# 2014_FDP_SCHEMA.net
KiCad netlist of a schematic drawn in Altium Designer
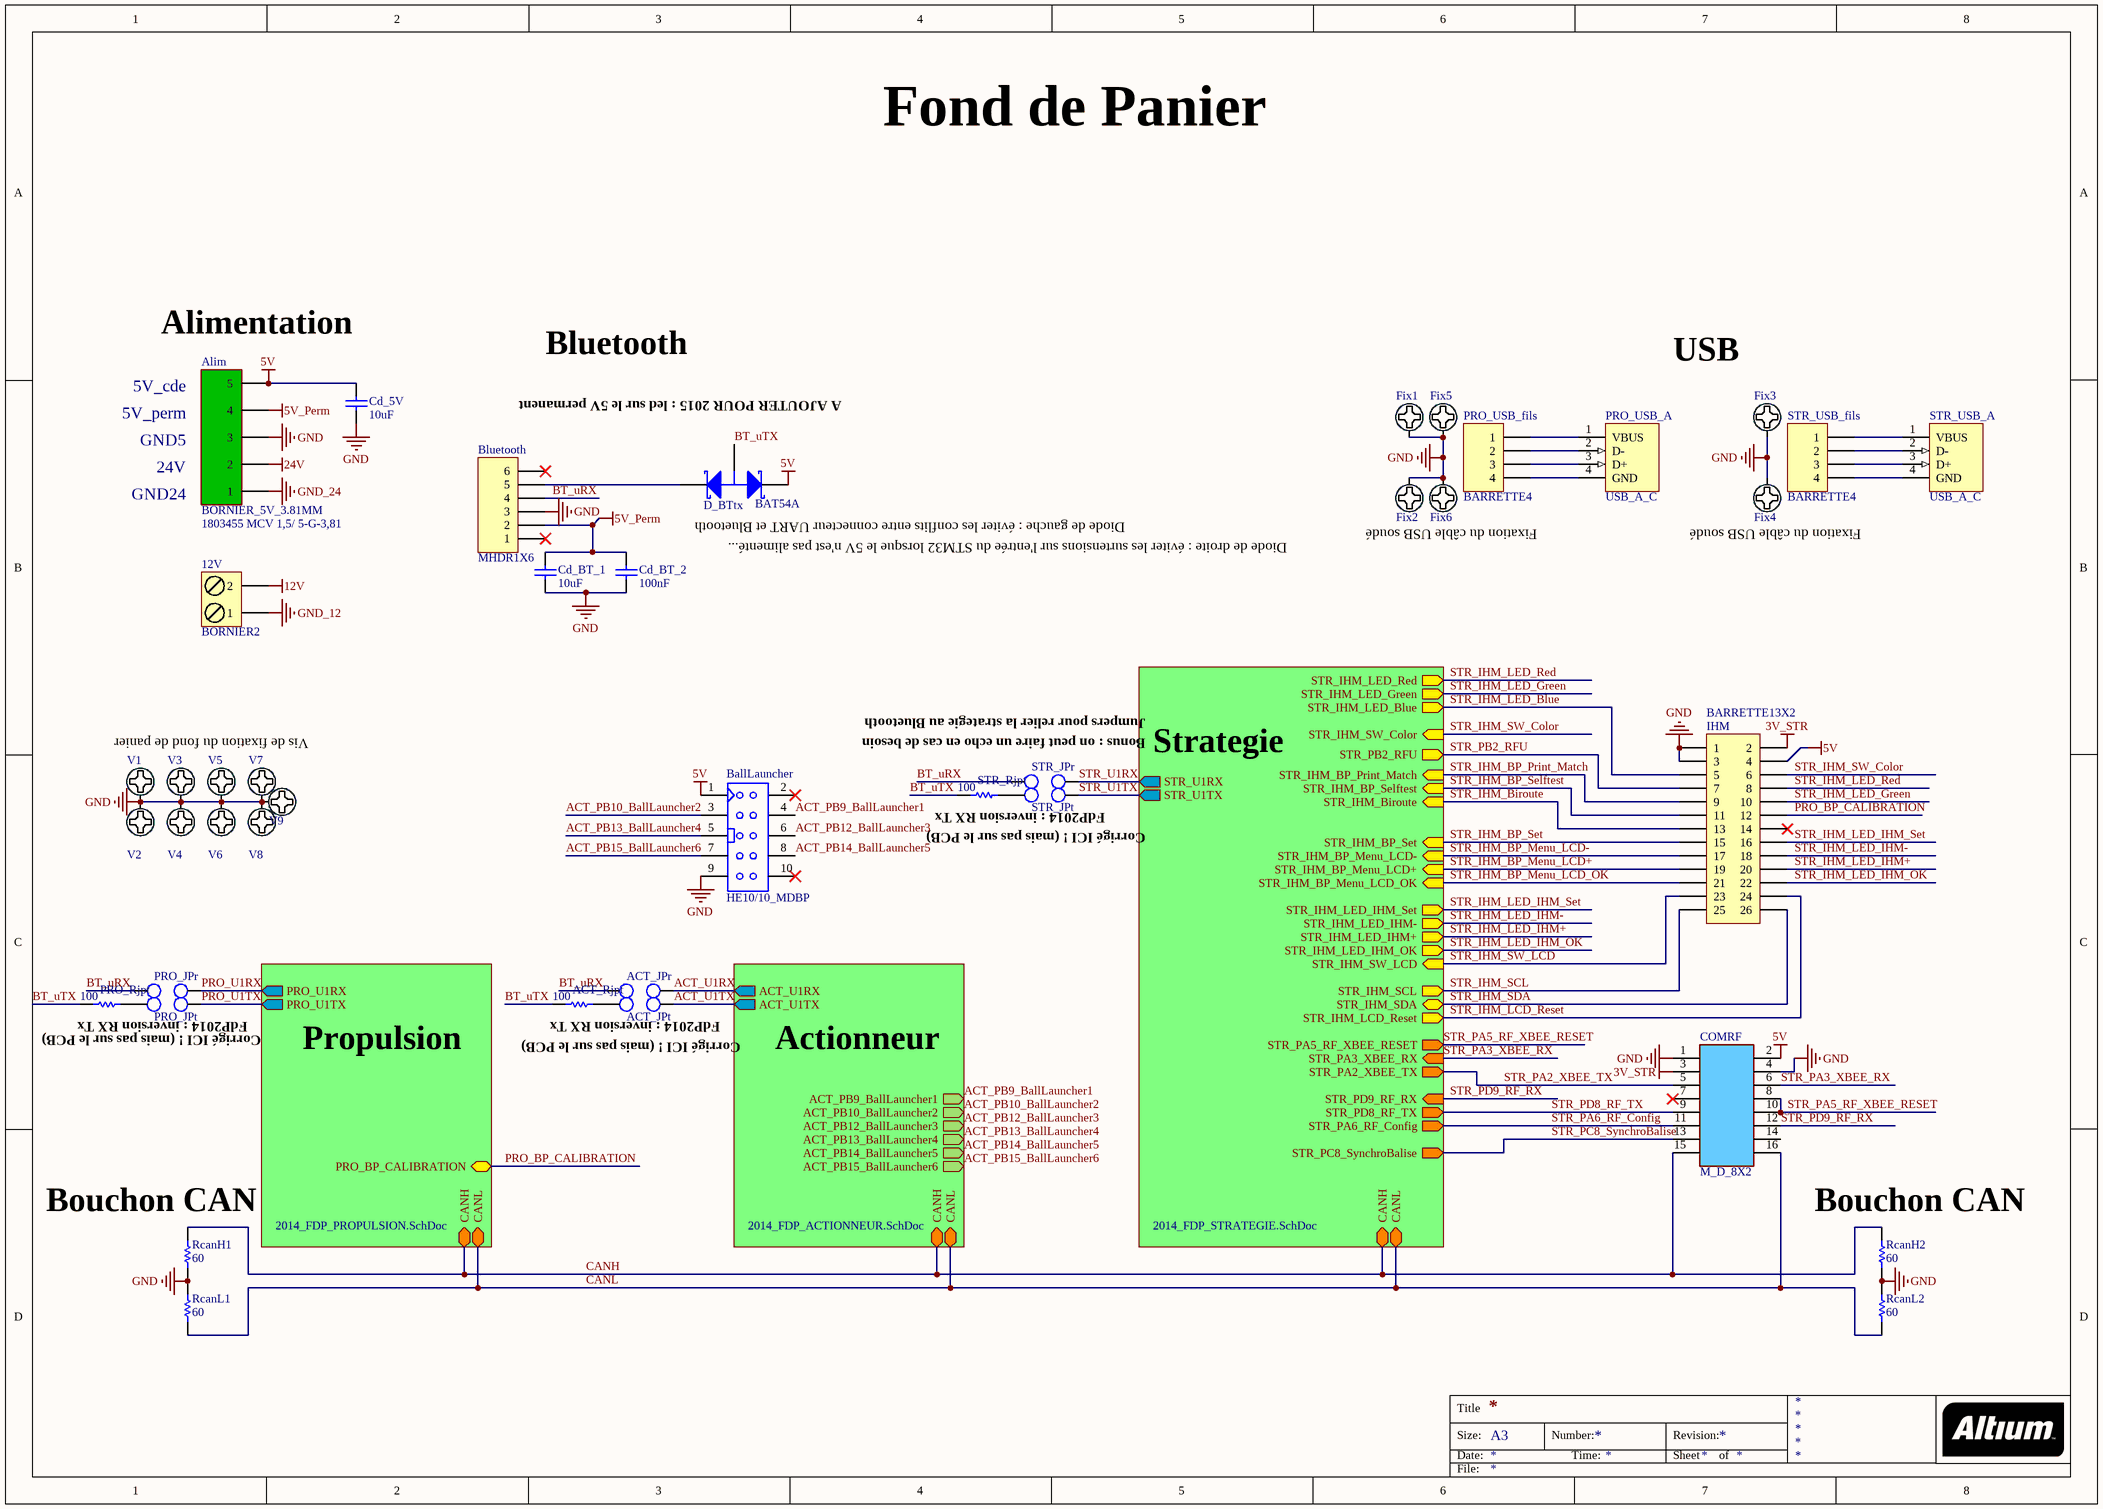
[diagram p0: 2014_FDP_SCHEMA.SchDoc]

(export (version "E")
  (design (tool "Eeschema 10.0.6"))
  (components
    (comp (ref "12V")
      (value "BORNIER2")
      (footprint "BORNIER2")
      (description "Terminal blocks, 2 pins, pitch=5mm")
      (libsource (lib "Connecteur") (part "BORNIER2"))
    )
    (comp (ref "ACT_JPr")
      (value "JUMPER2")
      (footprint "BARRETTE_2_M_D")
      (description "BARRETTE 2 CONTACTS 1 RANGEE MALE DROITE")
      (libsource (lib "connecteurs") (part "JUMPER2"))
    )
    (comp (ref "ACT_JPt")
      (value "JUMPER2")
      (footprint "BARRETTE_2_M_D")
      (description "BARRETTE 2 CONTACTS 1 RANGEE MALE DROITE")
      (libsource (lib "connecteurs") (part "JUMPER2"))
    )
    (comp (ref "ACT_Rjpt")
      (value "100")
      (footprint "R1206_N")
      (description "Resistor")
      (fields (field (name "PUBLISHER") "Altium Limited"))
      (libsource (lib "_ROBOT") (part "Resistor"))
    )
    (comp (ref "Alim")
      (value "BORNIER_5V_3.81MM")
      (footprint "BORNIER_5V_3.81MM")
      (fields (field (name "REF") "1803455 MCV 1,5/ 5-G-3,81"))
      (libsource (lib "Connecteur") (part "BORNIER_5V_3.81MM"))
    )
    (comp (ref "BallLauncher")
      (value "HE10/10_MALE_DROIT_BAS_PROFIL")
      (footprint "HE10/10_M_D_BP")
      (description "EMBASE HE10/10 MALE DROIT BAS PROFIL")
      (fields (field (name "TYPE") "HE10/10_MDBP"))
      (libsource (lib "connecteurs") (part "HE10/10_MALE_DROIT_BAS_PROFIL"))
    )
    (comp (ref "Bluetooth")
      (value "MHDR1X6")
      (footprint "HE14_6")
      (description "Header, 6-Pin")
      (fields (field (name "PUBLISHER") "Altium Limited"))
      (libsource (lib "Miscellaneous Connectors") (part "MHDR1X6"))
    )
    (comp (ref "Cd_5V")
      (value "10uF")
      (footprint "C1206_N")
      (description "Capacitor")
      (fields (field (name "PUBLISHER") "Altium Limited"))
      (libsource (lib "_ROBOT") (part "Condensateur"))
    )
    (comp (ref "Cd_BT_1")
      (value "10uF")
      (footprint "C1206_N")
      (description "Capacitor")
      (fields (field (name "PUBLISHER") "Altium Limited"))
      (libsource (lib "_ROBOT") (part "Condensateur"))
    )
    (comp (ref "Cd_BT_2")
      (value "100nF")
      (footprint "C0805_N")
      (description "Capacitor")
      (fields (field (name "PUBLISHER") "Altium Limited"))
      (libsource (lib "_ROBOT") (part "Condensateur"))
    )
    (comp (ref "COMRF")
      (value "BARRETTE_8 CONTACTS_2 RANGEES_MALE_DROITE")
      (footprint "HE10/16_M_D_B P")
      (fields (field (name "TYPE") "M_D_8X2"))
      (libsource (lib "connecteurs") (part "BARRETTE_8 CONTACTS_2 RANGEES_MALE_DROITE"))
    )
    (comp (ref "D_BTtx")
      (value "BAT54A")
      (footprint "SOT23-3N")
      (description "ZETEX - BAT54A - DIODE SCHOTTKY DOUBLE")
      (fields (field (name "MANUFACTURER") "ZETEX"))
      (libsource (lib "_ROBOT") (part "Diode Shottky double  BAT54A"))
    )
    (comp (ref "Fix1")
      (value "Pad_M3")
      (footprint "M3x6mm Torx")
      (description "Vis M3 X 6mm _TORX_Tête 6mm")
      (fields (field (name "PUBLISHER") "Damien Guitton"))
      (libsource (lib "DG_Mecanique") (part "Vis M3 X 6mm _TORX_Tête 6mm"))
    )
    (comp (ref "Fix2")
      (value "Pad_M3")
      (footprint "M3x6mm Torx")
      (description "Vis M3 X 6mm _TORX_Tête 6mm")
      (fields (field (name "PUBLISHER") "Damien Guitton"))
      (libsource (lib "DG_Mecanique") (part "Vis M3 X 6mm _TORX_Tête 6mm"))
    )
    (comp (ref "Fix3")
      (value "Pad_M3")
      (footprint "M3x6mm Torx")
      (description "Vis M3 X 6mm _TORX_Tête 6mm")
      (fields (field (name "PUBLISHER") "Damien Guitton"))
      (libsource (lib "DG_Mecanique") (part "Vis M3 X 6mm _TORX_Tête 6mm"))
    )
    (comp (ref "Fix4")
      (value "Pad_M3")
      (footprint "M3x6mm Torx")
      (description "Vis M3 X 6mm _TORX_Tête 6mm")
      (fields (field (name "PUBLISHER") "Damien Guitton"))
      (libsource (lib "DG_Mecanique") (part "Vis M3 X 6mm _TORX_Tête 6mm"))
    )
    (comp (ref "Fix5")
      (value "Pad_M3")
      (footprint "M3x6mm Torx")
      (description "Vis M3 X 6mm _TORX_Tête 6mm")
      (fields (field (name "PUBLISHER") "Damien Guitton"))
      (libsource (lib "DG_Mecanique") (part "Vis M3 X 6mm _TORX_Tête 6mm"))
    )
    (comp (ref "Fix6")
      (value "Pad_M3")
      (footprint "M3x6mm Torx")
      (description "Vis M3 X 6mm _TORX_Tête 6mm")
      (fields (field (name "PUBLISHER") "Damien Guitton"))
      (libsource (lib "DG_Mecanique") (part "Vis M3 X 6mm _TORX_Tête 6mm"))
    )
    (comp (ref "IHM")
      (value "BARRETTE13X2")
      (footprint "HE10/26_M_D_BP")
      (description "Header, 13-Pin, Dual row")
      (fields (field (name "PUBLISHER") "Altium Limited"))
      (libsource (lib "Connecteur") (part "BARRETTE13X2"))
    )
    (comp (ref "PRO_JPr")
      (value "JUMPER2")
      (footprint "BARRETTE_2_M_D")
      (description "BARRETTE 2 CONTACTS 1 RANGEE MALE DROITE")
      (libsource (lib "connecteurs") (part "JUMPER2"))
    )
    (comp (ref "PRO_JPt")
      (value "JUMPER2")
      (footprint "BARRETTE_2_M_D")
      (description "BARRETTE 2 CONTACTS 1 RANGEE MALE DROITE")
      (libsource (lib "connecteurs") (part "JUMPER2"))
    )
    (comp (ref "PRO_Rjpt")
      (value "100")
      (footprint "R1206_N")
      (description "Resistor")
      (fields (field (name "PUBLISHER") "Altium Limited"))
      (libsource (lib "_ROBOT") (part "Resistor"))
    )
    (comp (ref "PRO_USB_A")
      (value "USB_A_COUDEE")
      (footprint "USB_A_C")
      (description "EMBASE USB TRAVERSANTE TYPE A COUDEE")
      (fields (field (name "TYPE") "USB_A_C"))
      (libsource (lib "connecteurs") (part "USB_A_COUDEE"))
    )
    (comp (ref "PRO_USB_fils")
      (value "BARRETTE4")
      (footprint "HE14_4")
      (description "Header, 4-Pin")
      (fields (field (name "PUBLISHER") "Altium Limited"))
      (libsource (lib "Connecteur") (part "BARRETTE4"))
    )
    (comp (ref "RcanH1")
      (value "60")
      (footprint "R1206_N")
      (description "Resistor")
      (fields (field (name "PUBLISHER") "Altium Limited"))
      (libsource (lib "_ROBOT") (part "Resistor"))
    )
    (comp (ref "RcanH2")
      (value "60")
      (footprint "R1206_N")
      (description "Resistor")
      (fields (field (name "PUBLISHER") "Altium Limited"))
      (libsource (lib "_ROBOT") (part "Resistor"))
    )
    (comp (ref "RcanL1")
      (value "60")
      (footprint "R1206_N")
      (description "Resistor")
      (fields (field (name "PUBLISHER") "Altium Limited"))
      (libsource (lib "_ROBOT") (part "Resistor"))
    )
    (comp (ref "RcanL2")
      (value "60")
      (footprint "R1206_N")
      (description "Resistor")
      (fields (field (name "PUBLISHER") "Altium Limited"))
      (libsource (lib "_ROBOT") (part "Resistor"))
    )
    (comp (ref "STR_JPr")
      (value "JUMPER2")
      (footprint "BARRETTE_2_M_D")
      (description "BARRETTE 2 CONTACTS 1 RANGEE MALE DROITE")
      (libsource (lib "connecteurs") (part "JUMPER2"))
    )
    (comp (ref "STR_JPt")
      (value "JUMPER2")
      (footprint "BARRETTE_2_M_D")
      (description "BARRETTE 2 CONTACTS 1 RANGEE MALE DROITE")
      (libsource (lib "connecteurs") (part "JUMPER2"))
    )
    (comp (ref "STR_Rjpt")
      (value "100")
      (footprint "R1206_N")
      (description "Resistor")
      (fields (field (name "PUBLISHER") "Altium Limited"))
      (libsource (lib "_ROBOT") (part "Resistor"))
    )
    (comp (ref "STR_USB_A")
      (value "USB_A_COUDEE")
      (footprint "USB_A_C")
      (description "EMBASE USB TRAVERSANTE TYPE A COUDEE")
      (fields (field (name "TYPE") "USB_A_C"))
      (libsource (lib "connecteurs") (part "USB_A_COUDEE"))
    )
    (comp (ref "STR_USB_fils")
      (value "BARRETTE4")
      (footprint "HE14_4")
      (description "Header, 4-Pin")
      (fields (field (name "PUBLISHER") "Altium Limited"))
      (libsource (lib "Connecteur") (part "BARRETTE4"))
    )
    (comp (ref "V1")
      (value "Pad_M3")
      (footprint "M3x6mm Torx")
      (description "Vis M3 X 6mm _TORX_Tête 6mm")
      (fields (field (name "PUBLISHER") "Damien Guitton"))
      (libsource (lib "DG_Mecanique") (part "Vis M3 X 6mm _TORX_Tête 6mm"))
    )
    (comp (ref "V2")
      (value "Pad_M3")
      (footprint "M3x6mm Torx")
      (description "Vis M3 X 6mm _TORX_Tête 6mm")
      (fields (field (name "PUBLISHER") "Damien Guitton"))
      (libsource (lib "DG_Mecanique") (part "Vis M3 X 6mm _TORX_Tête 6mm"))
    )
    (comp (ref "V3")
      (value "Pad_M3")
      (footprint "M3x6mm Torx")
      (description "Vis M3 X 6mm _TORX_Tête 6mm")
      (fields (field (name "PUBLISHER") "Damien Guitton"))
      (libsource (lib "DG_Mecanique") (part "Vis M3 X 6mm _TORX_Tête 6mm"))
    )
    (comp (ref "V4")
      (value "Pad_M3")
      (footprint "M3x6mm Torx")
      (description "Vis M3 X 6mm _TORX_Tête 6mm")
      (fields (field (name "PUBLISHER") "Damien Guitton"))
      (libsource (lib "DG_Mecanique") (part "Vis M3 X 6mm _TORX_Tête 6mm"))
    )
    (comp (ref "V5")
      (value "Pad_M3")
      (footprint "M3x6mm Torx")
      (description "Vis M3 X 6mm _TORX_Tête 6mm")
      (fields (field (name "PUBLISHER") "Damien Guitton"))
      (libsource (lib "DG_Mecanique") (part "Vis M3 X 6mm _TORX_Tête 6mm"))
    )
    (comp (ref "V6")
      (value "Pad_M3")
      (footprint "M3x6mm Torx")
      (description "Vis M3 X 6mm _TORX_Tête 6mm")
      (fields (field (name "PUBLISHER") "Damien Guitton"))
      (libsource (lib "DG_Mecanique") (part "Vis M3 X 6mm _TORX_Tête 6mm"))
    )
    (comp (ref "V7")
      (value "Pad_M3")
      (footprint "M3x6mm Torx")
      (description "Vis M3 X 6mm _TORX_Tête 6mm")
      (fields (field (name "PUBLISHER") "Damien Guitton"))
      (libsource (lib "DG_Mecanique") (part "Vis M3 X 6mm _TORX_Tête 6mm"))
    )
    (comp (ref "V8")
      (value "Pad_M3")
      (footprint "M3x6mm Torx")
      (description "Vis M3 X 6mm _TORX_Tête 6mm")
      (fields (field (name "PUBLISHER") "Damien Guitton"))
      (libsource (lib "DG_Mecanique") (part "Vis M3 X 6mm _TORX_Tête 6mm"))
    )
    (comp (ref "V9")
      (value "Pad_M3")
      (footprint "M3x6mm Torx")
      (description "Vis M3 X 6mm _TORX_Tête 6mm")
      (fields (field (name "PUBLISHER") "Damien Guitton"))
      (libsource (lib "DG_Mecanique") (part "Vis M3 X 6mm _TORX_Tête 6mm"))
    )
  )
  (nets
    (net (code "1") (name "/ACT_PB9_BallLauncher1") (class "Default")
      (node (ref "BallLauncher") (pin "4") (pinfunction "4_4") (pintype "passive"))
    )
    (net (code "2") (name "/ACT_PB10_BallLauncher2") (class "Default")
      (node (ref "BallLauncher") (pin "3") (pinfunction "3_3") (pintype "passive"))
    )
    (net (code "3") (name "/ACT_PB12_BallLauncher3") (class "Default")
      (node (ref "BallLauncher") (pin "6") (pinfunction "6_6") (pintype "passive"))
    )
    (net (code "4") (name "/ACT_PB13_BallLauncher4") (class "Default")
      (node (ref "BallLauncher") (pin "5") (pinfunction "5_5") (pintype "passive"))
    )
    (net (code "5") (name "/ACT_PB14_BallLauncher5") (class "Default")
      (node (ref "BallLauncher") (pin "8") (pinfunction "8_8") (pintype "passive"))
    )
    (net (code "6") (name "/ACT_PB15_BallLauncher6") (class "Default")
      (node (ref "BallLauncher") (pin "7") (pinfunction "7_7") (pintype "passive"))
    )
    (net (code "7") (name "/ACT_U1RX") (class "Default")
      (node (ref "ACT_JPr") (pin "2") (pinfunction "2_2") (pintype "passive"))
    )
    (net (code "8") (name "/ACT_U1TX") (class "Default")
      (node (ref "ACT_JPt") (pin "2") (pinfunction "2_2") (pintype "passive"))
    )
    (net (code "9") (name "/BT_uRX") (class "Default")
      (node (ref "ACT_JPr") (pin "1") (pinfunction "1_1") (pintype "passive"))
      (node (ref "Bluetooth") (pin "4") (pinfunction "4_4") (pintype "passive"))
      (node (ref "PRO_JPr") (pin "1") (pinfunction "1_1") (pintype "passive"))
      (node (ref "STR_JPr") (pin "1") (pinfunction "1_1") (pintype "passive"))
    )
    (net (code "10") (name "/BT_uTX") (class "Default")
      (node (ref "ACT_Rjpt") (pin "2") (pinfunction "2_2") (pintype "passive"))
      (node (ref "D_BTtx") (pin "3") (pinfunction "A_3") (pintype "passive"))
      (node (ref "PRO_Rjpt") (pin "2") (pinfunction "2_2") (pintype "passive"))
      (node (ref "STR_Rjpt") (pin "2") (pinfunction "2_2") (pintype "passive"))
    )
    (net (code "11") (name "/CANH") (class "Default")
      (node (ref "COMRF") (pin "15") (pinfunction "15_15") (pintype "passive"))
      (node (ref "RcanH1") (pin "2") (pinfunction "2_2") (pintype "passive"))
      (node (ref "RcanH2") (pin "1") (pinfunction "1_1") (pintype "passive"))
    )
    (net (code "12") (name "/CANL") (class "Default")
      (node (ref "COMRF") (pin "16") (pinfunction "16_16") (pintype "passive"))
      (node (ref "RcanL1") (pin "1") (pinfunction "1_1") (pintype "passive"))
      (node (ref "RcanL2") (pin "1") (pinfunction "1_1") (pintype "passive"))
    )
    (net (code "13") (name "/PRO_BP_CALIBRATION") (class "Default")
      (node (ref "IHM") (pin "12") (pinfunction "12_12") (pintype "passive"))
    )
    (net (code "14") (name "/PRO_U1RX") (class "Default")
      (node (ref "PRO_JPr") (pin "2") (pinfunction "2_2") (pintype "passive"))
    )
    (net (code "15") (name "/PRO_U1TX") (class "Default")
      (node (ref "PRO_JPt") (pin "2") (pinfunction "2_2") (pintype "passive"))
    )
    (net (code "16") (name "/STR_IHM_BP_Menu_LCD+") (class "Default")
      (node (ref "IHM") (pin "19") (pinfunction "19_19") (pintype "passive"))
    )
    (net (code "17") (name "/STR_IHM_BP_Menu_LCD-") (class "Default")
      (node (ref "IHM") (pin "17") (pinfunction "17_17") (pintype "passive"))
    )
    (net (code "18") (name "/STR_IHM_BP_Menu_LCD_OK") (class "Default")
      (node (ref "IHM") (pin "21") (pinfunction "21_21") (pintype "passive"))
    )
    (net (code "19") (name "/STR_IHM_BP_Print_Match") (class "Default")
      (node (ref "IHM") (pin "9") (pinfunction "9_9") (pintype "passive"))
    )
    (net (code "20") (name "/STR_IHM_BP_Selftest") (class "Default")
      (node (ref "IHM") (pin "11") (pinfunction "11_11") (pintype "passive"))
    )
    (net (code "21") (name "/STR_IHM_BP_Set") (class "Default")
      (node (ref "IHM") (pin "15") (pinfunction "15_15") (pintype "passive"))
    )
    (net (code "22") (name "/STR_IHM_Biroute") (class "Default")
      (node (ref "IHM") (pin "13") (pinfunction "13_13") (pintype "passive"))
    )
    (net (code "23") (name "/STR_IHM_LCD_Reset") (class "Default")
      (node (ref "IHM") (pin "24") (pinfunction "24_24") (pintype "passive"))
    )
    (net (code "24") (name "/STR_IHM_LED_Blue") (class "Default")
      (node (ref "IHM") (pin "5") (pinfunction "5_5") (pintype "passive"))
    )
    (net (code "25") (name "/STR_IHM_LED_Green") (class "Default")
      (node (ref "IHM") (pin "10") (pinfunction "10_10") (pintype "passive"))
    )
    (net (code "26") (name "/STR_IHM_LED_IHM+") (class "Default")
      (node (ref "IHM") (pin "20") (pinfunction "20_20") (pintype "passive"))
    )
    (net (code "27") (name "/STR_IHM_LED_IHM-") (class "Default")
      (node (ref "IHM") (pin "18") (pinfunction "18_18") (pintype "passive"))
    )
    (net (code "28") (name "/STR_IHM_LED_IHM_OK") (class "Default")
      (node (ref "IHM") (pin "22") (pinfunction "22_22") (pintype "passive"))
    )
    (net (code "29") (name "/STR_IHM_LED_IHM_Set") (class "Default")
      (node (ref "IHM") (pin "16") (pinfunction "16_16") (pintype "passive"))
    )
    (net (code "30") (name "/STR_IHM_LED_Red") (class "Default")
      (node (ref "IHM") (pin "8") (pinfunction "8_8") (pintype "passive"))
    )
    (net (code "31") (name "/STR_IHM_SCL") (class "Default")
      (node (ref "IHM") (pin "25") (pinfunction "25_25") (pintype "passive"))
    )
    (net (code "32") (name "/STR_IHM_SDA") (class "Default")
      (node (ref "IHM") (pin "26") (pinfunction "26_26") (pintype "passive"))
    )
    (net (code "33") (name "/STR_IHM_SW_Color") (class "Default")
      (node (ref "IHM") (pin "6") (pinfunction "6_6") (pintype "passive"))
    )
    (net (code "34") (name "/STR_IHM_SW_LCD") (class "Default")
      (node (ref "IHM") (pin "23") (pinfunction "23_23") (pintype "passive"))
    )
    (net (code "35") (name "/STR_PA2_XBEE_TX") (class "Default")
      (node (ref "COMRF") (pin "5") (pinfunction "5_5") (pintype "passive"))
    )
    (net (code "36") (name "/STR_PA3_XBEE_RX") (class "Default")
      (node (ref "COMRF") (pin "6") (pinfunction "6_6") (pintype "passive"))
    )
    (net (code "37") (name "/STR_PA5_RF_XBEE_RESET") (class "Default")
      (node (ref "COMRF") (pin "10") (pinfunction "10_10") (pintype "passive"))
      (node (ref "COMRF") (pin "8") (pinfunction "8_8") (pintype "passive"))
    )
    (net (code "38") (name "/STR_PA6_RF_Config") (class "Default")
      (node (ref "COMRF") (pin "11") (pinfunction "11_11") (pintype "passive"))
    )
    (net (code "39") (name "/STR_PB2_RFU") (class "Default")
      (node (ref "IHM") (pin "7") (pinfunction "7_7") (pintype "passive"))
    )
    (net (code "40") (name "/STR_PC8_SynchroBalise") (class "Default")
      (node (ref "COMRF") (pin "13") (pinfunction "13_13") (pintype "passive"))
    )
    (net (code "41") (name "/STR_PD8_RF_TX") (class "Default")
      (node (ref "COMRF") (pin "9") (pinfunction "9_9") (pintype "passive"))
    )
    (net (code "42") (name "/STR_PD9_RF_RX") (class "Default")
      (node (ref "COMRF") (pin "12") (pinfunction "12_12") (pintype "passive"))
    )
    (net (code "43") (name "/STR_U1RX") (class "Default")
      (node (ref "STR_JPr") (pin "2") (pinfunction "2_2") (pintype "passive"))
    )
    (net (code "44") (name "/STR_U1TX") (class "Default")
      (node (ref "STR_JPt") (pin "2") (pinfunction "2_2") (pintype "passive"))
    )
    (net (code "45") (name "3V_STR") (class "Default")
      (node (ref "COMRF") (pin "3") (pinfunction "3_3") (pintype "passive"))
      (node (ref "IHM") (pin "2") (pinfunction "2_2") (pintype "passive"))
    )
    (net (code "46") (name "5V") (class "Default")
      (node (ref "Alim") (pin "5") (pinfunction "5_5") (pintype "passive"))
      (node (ref "BallLauncher") (pin "1") (pinfunction "1_1") (pintype "passive"))
      (node (ref "COMRF") (pin "2") (pinfunction "2_2") (pintype "passive"))
      (node (ref "Cd_5V") (pin "2") (pinfunction "2_2") (pintype "passive"))
      (node (ref "D_BTtx") (pin "2") (pinfunction "K2_2") (pintype "passive"))
      (node (ref "IHM") (pin "4") (pinfunction "4_4") (pintype "passive"))
    )
    (net (code "47") (name "5V_Perm") (class "Default")
      (node (ref "Alim") (pin "4") (pinfunction "4_4") (pintype "passive"))
      (node (ref "Bluetooth") (pin "2") (pinfunction "2_2") (pintype "passive"))
      (node (ref "Cd_BT_1") (pin "2") (pinfunction "2_2") (pintype "passive"))
      (node (ref "Cd_BT_2") (pin "2") (pinfunction "2_2") (pintype "passive"))
    )
    (net (code "48") (name "12V") (class "Default")
      (node (ref "12V") (pin "2") (pinfunction "2_2") (pintype "passive"))
    )
    (net (code "49") (name "24V") (class "Default")
      (node (ref "Alim") (pin "2") (pinfunction "2_2") (pintype "passive"))
    )
    (net (code "50") (name "GND") (class "Default")
      (node (ref "Alim") (pin "3") (pinfunction "3_3") (pintype "passive"))
      (node (ref "BallLauncher") (pin "9") (pinfunction "9_9") (pintype "passive"))
      (node (ref "Bluetooth") (pin "3") (pinfunction "3_3") (pintype "passive"))
      (node (ref "COMRF") (pin "1") (pinfunction "1_1") (pintype "passive"))
      (node (ref "COMRF") (pin "4") (pinfunction "4_4") (pintype "passive"))
      (node (ref "Cd_5V") (pin "1") (pinfunction "1_1") (pintype "passive"))
      (node (ref "Cd_BT_1") (pin "1") (pinfunction "1_1") (pintype "passive"))
      (node (ref "Cd_BT_2") (pin "1") (pinfunction "1_1") (pintype "passive"))
      (node (ref "Fix1") (pin "1") (pinfunction "1_1") (pintype "passive"))
      (node (ref "Fix2") (pin "1") (pinfunction "1_1") (pintype "passive"))
      (node (ref "Fix3") (pin "1") (pinfunction "1_1") (pintype "passive"))
      (node (ref "Fix4") (pin "1") (pinfunction "1_1") (pintype "passive"))
      (node (ref "Fix5") (pin "1") (pinfunction "1_1") (pintype "passive"))
      (node (ref "Fix6") (pin "1") (pinfunction "1_1") (pintype "passive"))
      (node (ref "IHM") (pin "1") (pinfunction "1_1") (pintype "passive"))
      (node (ref "IHM") (pin "3") (pinfunction "3_3") (pintype "passive"))
      (node (ref "RcanH1") (pin "1") (pinfunction "1_1") (pintype "passive"))
      (node (ref "RcanH2") (pin "2") (pinfunction "2_2") (pintype "passive"))
      (node (ref "RcanL1") (pin "2") (pinfunction "2_2") (pintype "passive"))
      (node (ref "RcanL2") (pin "2") (pinfunction "2_2") (pintype "passive"))
      (node (ref "V1") (pin "1") (pinfunction "1_1") (pintype "passive"))
      (node (ref "V2") (pin "1") (pinfunction "1_1") (pintype "passive"))
      (node (ref "V3") (pin "1") (pinfunction "1_1") (pintype "passive"))
      (node (ref "V4") (pin "1") (pinfunction "1_1") (pintype "passive"))
      (node (ref "V5") (pin "1") (pinfunction "1_1") (pintype "passive"))
      (node (ref "V6") (pin "1") (pinfunction "1_1") (pintype "passive"))
      (node (ref "V7") (pin "1") (pinfunction "1_1") (pintype "passive"))
      (node (ref "V8") (pin "1") (pinfunction "1_1") (pintype "passive"))
      (node (ref "V9") (pin "1") (pinfunction "1_1") (pintype "passive"))
    )
    (net (code "51") (name "GND_12") (class "Default")
      (node (ref "12V") (pin "1") (pinfunction "1_1") (pintype "passive"))
    )
    (net (code "52") (name "GND_24") (class "Default")
      (node (ref "Alim") (pin "1") (pinfunction "1_1") (pintype "passive"))
    )
    (net (code "53") (name "Net-(ACT_JPt-Pad1)") (class "Default")
      (node (ref "ACT_JPt") (pin "1") (pinfunction "1_1") (pintype "passive"))
      (node (ref "ACT_Rjpt") (pin "1") (pinfunction "1_1") (pintype "passive"))
    )
    (net (code "54") (name "Net-(D_BTtx-K1)") (class "Default")
      (node (ref "Bluetooth") (pin "5") (pinfunction "5_5") (pintype "passive"))
      (node (ref "D_BTtx") (pin "1") (pinfunction "K1_1") (pintype "passive"))
    )
    (net (code "55") (name "Net-(PRO_JPt-Pad1)") (class "Default")
      (node (ref "PRO_JPt") (pin "1") (pinfunction "1_1") (pintype "passive"))
      (node (ref "PRO_Rjpt") (pin "1") (pinfunction "1_1") (pintype "passive"))
    )
    (net (code "56") (name "Net-(PRO_USB_A-D+)") (class "Default")
      (node (ref "PRO_USB_A") (pin "3") (pinfunction "D+_3") (pintype "input"))
      (node (ref "PRO_USB_fils") (pin "3") (pinfunction "3_3") (pintype "passive"))
    )
    (net (code "57") (name "Net-(PRO_USB_A-D-)") (class "Default")
      (node (ref "PRO_USB_A") (pin "2") (pinfunction "D-_2") (pintype "input"))
      (node (ref "PRO_USB_fils") (pin "2") (pinfunction "2_2") (pintype "passive"))
    )
    (net (code "58") (name "Net-(PRO_USB_A-GND)") (class "Default")
      (node (ref "PRO_USB_A") (pin "4") (pinfunction "GND_4") (pintype "power_in"))
      (node (ref "PRO_USB_fils") (pin "4") (pinfunction "4_4") (pintype "passive"))
    )
    (net (code "59") (name "Net-(PRO_USB_A-VBUS)") (class "Default")
      (node (ref "PRO_USB_A") (pin "1") (pinfunction "VBUS_1") (pintype "power_in"))
      (node (ref "PRO_USB_fils") (pin "1") (pinfunction "1_1") (pintype "passive"))
    )
    (net (code "60") (name "Net-(STR_JPt-Pad1)") (class "Default")
      (node (ref "STR_JPt") (pin "1") (pinfunction "1_1") (pintype "passive"))
      (node (ref "STR_Rjpt") (pin "1") (pinfunction "1_1") (pintype "passive"))
    )
    (net (code "61") (name "Net-(STR_USB_A-D+)") (class "Default")
      (node (ref "STR_USB_A") (pin "3") (pinfunction "D+_3") (pintype "input"))
      (node (ref "STR_USB_fils") (pin "3") (pinfunction "3_3") (pintype "passive"))
    )
    (net (code "62") (name "Net-(STR_USB_A-D-)") (class "Default")
      (node (ref "STR_USB_A") (pin "2") (pinfunction "D-_2") (pintype "input"))
      (node (ref "STR_USB_fils") (pin "2") (pinfunction "2_2") (pintype "passive"))
    )
    (net (code "63") (name "Net-(STR_USB_A-GND)") (class "Default")
      (node (ref "STR_USB_A") (pin "4") (pinfunction "GND_4") (pintype "power_in"))
      (node (ref "STR_USB_fils") (pin "4") (pinfunction "4_4") (pintype "passive"))
    )
    (net (code "64") (name "Net-(STR_USB_A-VBUS)") (class "Default")
      (node (ref "STR_USB_A") (pin "1") (pinfunction "VBUS_1") (pintype "power_in"))
      (node (ref "STR_USB_fils") (pin "1") (pinfunction "1_1") (pintype "passive"))
    )
    (net (code "65") (name "unconnected-(BallLauncher-Pad2)") (class "Default")
      (node (ref "BallLauncher") (pin "2") (pinfunction "2_2") (pintype "passive+no_connect"))
    )
    (net (code "66") (name "unconnected-(BallLauncher-Pad10)") (class "Default")
      (node (ref "BallLauncher") (pin "10") (pinfunction "10_10") (pintype "passive+no_connect"))
    )
    (net (code "67") (name "unconnected-(Bluetooth-Pad1)") (class "Default")
      (node (ref "Bluetooth") (pin "1") (pinfunction "1_1") (pintype "passive+no_connect"))
    )
    (net (code "68") (name "unconnected-(Bluetooth-Pad6)") (class "Default")
      (node (ref "Bluetooth") (pin "6") (pinfunction "6_6") (pintype "passive+no_connect"))
    )
    (net (code "69") (name "unconnected-(COMRF-Pad7)") (class "Default")
      (node (ref "COMRF") (pin "7") (pinfunction "7_7") (pintype "passive+no_connect"))
    )
    (net (code "70") (name "unconnected-(COMRF-Pad14)") (class "Default")
      (node (ref "COMRF") (pin "14") (pinfunction "14_14") (pintype "passive"))
    )
    (net (code "71") (name "unconnected-(IHM-Pad14)") (class "Default")
      (node (ref "IHM") (pin "14") (pinfunction "14_14") (pintype "passive+no_connect"))
    )
  )
)
